# LDLN025_1V8_Regulator.net
KiCad netlist of a schematic drawn in Altium Designer
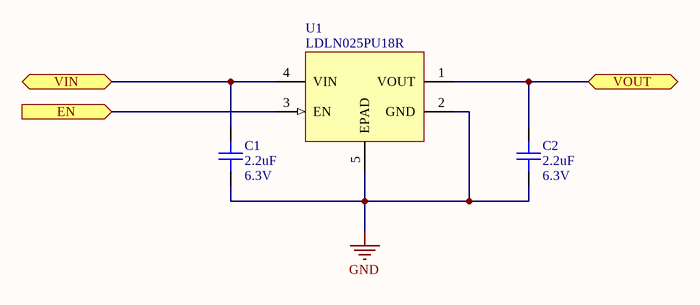
[diagram p0: LDLN025_1V8_Regulator.SchDoc]

(export (version "E")
  (design (tool "Eeschema 10.0.6"))
  (components
    (comp (ref "C1")
      (value "CAP CER 2.2UF 6.3V X5R 0402")
      (footprint "C0402")
      (description "2.2µF ±20% 6.3V Ceramic Capacitor X5R 0402 (1005 Metric)")
      (fields
        (field (name "MANUFACTURER") "Murata")
        (field (name "MANUFACTURER PART NUMBER") "GRM155R60J225ME15D")
        (field (name "CAPACITANCE") "2.2uF")
        (field (name "VOLTAGE") "6.3V")
      )
      (libsource (lib "capacitors_smd") (part "CAP CER 2.2UF 6.3V X5R 0402"))
    )
    (comp (ref "C2")
      (value "CAP CER 2.2UF 6.3V X5R 0402")
      (footprint "C0402")
      (description "2.2µF ±20% 6.3V Ceramic Capacitor X5R 0402 (1005 Metric)")
      (fields
        (field (name "MANUFACTURER") "Murata")
        (field (name "MANUFACTURER PART NUMBER") "GRM155R60J225ME15D")
        (field (name "CAPACITANCE") "2.2uF")
        (field (name "VOLTAGE") "6.3V")
      )
      (libsource (lib "capacitors_smd") (part "CAP CER 2.2UF 6.3V X5R 0402"))
    )
    (comp (ref "U1")
      (value "LDLN025PU18R")
      (footprint "DFN65P100X40-4N")
      (description "Linear Voltage Regulator IC 1 Output 250mA 4-DFN (1x1)")
      (fields (field (name "MANUFACTURER") "STMicroelectronics"))
      (libsource (lib "voltage_regulators_linear") (part "IC LDLN025 REG LINEAR 1.8V 250MA 4DFN"))
    )
  )
  (nets
    (net (code "1") (name "/EN") (class "Default")
      (node (ref "U1") (pin "3") (pinfunction "EN_3") (pintype "input"))
    )
    (net (code "2") (name "/VIN") (class "Default")
      (node (ref "C1") (pin "2") (pinfunction "2_2") (pintype "passive"))
      (node (ref "U1") (pin "4") (pinfunction "VIN_4") (pintype "power_in"))
    )
    (net (code "3") (name "/VOUT") (class "Default")
      (node (ref "C2") (pin "2") (pinfunction "2_2") (pintype "passive"))
      (node (ref "U1") (pin "1") (pinfunction "VOUT_1") (pintype "power_in"))
    )
    (net (code "4") (name "GND") (class "Default")
      (node (ref "C1") (pin "1") (pinfunction "1_1") (pintype "passive"))
      (node (ref "C2") (pin "1") (pinfunction "1_1") (pintype "passive"))
      (node (ref "U1") (pin "2") (pinfunction "GND_2") (pintype "power_in"))
      (node (ref "U1") (pin "5") (pinfunction "EPAD_5") (pintype "power_in"))
    )
  )
)
